# MirrorController.net
KiCad netlist of a schematic drawn in EAGLE
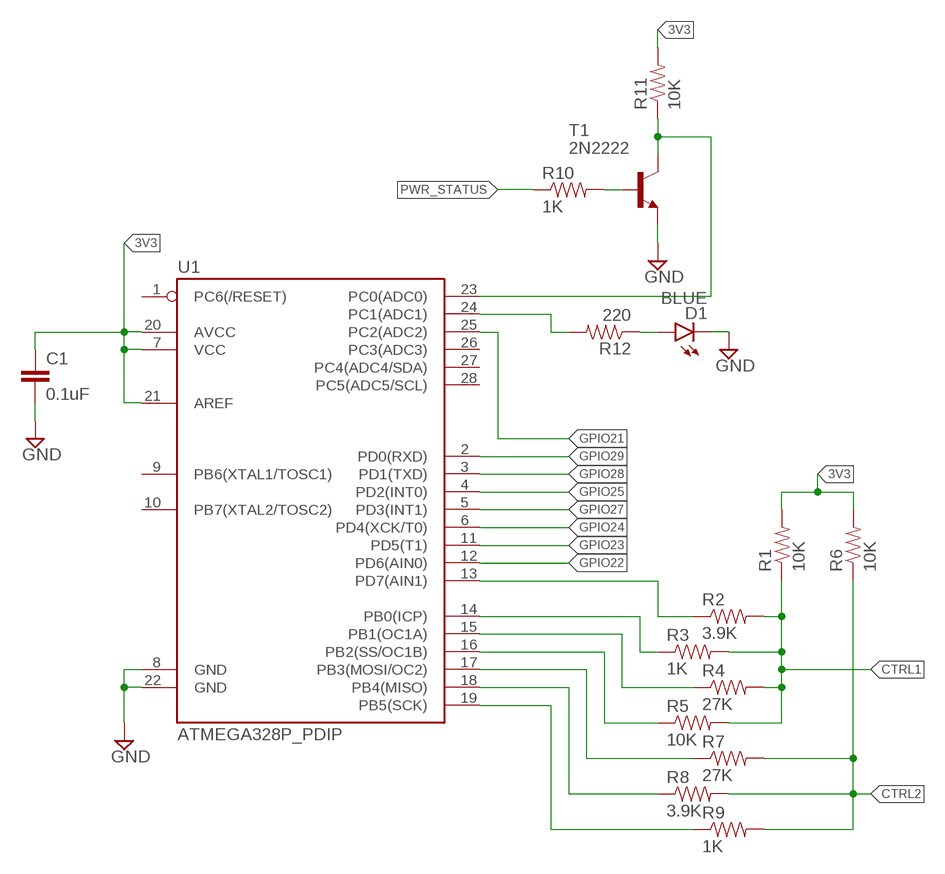
[diagram p0: schematic, sheet 1]

(export (version "E")
  (design (tool "Eeschema 10.0.6"))
  (components
    (comp (ref "C1")
      (value "0.1uF")
      (footprint "eagle-import:CAP-PTH-SMALL")
      (libsource (lib "eagle-import") (part "CAPPTH"))
    )
    (comp (ref "D1")
      (value "BLUE")
      (footprint "eagle-import:LED5MM")
      (libsource (lib "eagle-import") (part "LED5MM"))
    )
    (comp (ref "R1")
      (value "10K")
      (footprint "eagle-import:AXIAL-0.4")
      (libsource (lib "eagle-import") (part "RESISTORPTH-1/4W"))
    )
    (comp (ref "R2")
      (value "3.9K")
      (footprint "eagle-import:AXIAL-0.4")
      (libsource (lib "eagle-import") (part "RESISTORPTH-1/4W"))
    )
    (comp (ref "R3")
      (value "1K")
      (footprint "eagle-import:AXIAL-0.4")
      (libsource (lib "eagle-import") (part "RESISTORPTH-1/4W"))
    )
    (comp (ref "R4")
      (value "27K")
      (footprint "eagle-import:AXIAL-0.4")
      (libsource (lib "eagle-import") (part "RESISTORPTH-1/4W"))
    )
    (comp (ref "R5")
      (value "10K")
      (footprint "eagle-import:AXIAL-0.4")
      (libsource (lib "eagle-import") (part "RESISTORPTH-1/4W"))
    )
    (comp (ref "R6")
      (value "10K")
      (footprint "eagle-import:AXIAL-0.4")
      (libsource (lib "eagle-import") (part "RESISTORPTH-1/4W"))
    )
    (comp (ref "R7")
      (value "27K")
      (footprint "eagle-import:AXIAL-0.4")
      (libsource (lib "eagle-import") (part "RESISTORPTH-1/4W"))
    )
    (comp (ref "R8")
      (value "3.9K")
      (footprint "eagle-import:AXIAL-0.4")
      (libsource (lib "eagle-import") (part "RESISTORPTH-1/4W"))
    )
    (comp (ref "R9")
      (value "1K")
      (footprint "eagle-import:AXIAL-0.4")
      (libsource (lib "eagle-import") (part "RESISTORPTH-1/4W"))
    )
    (comp (ref "R10")
      (value "1K")
      (footprint "eagle-import:AXIAL-0.4")
      (libsource (lib "eagle-import") (part "RESISTORPTH-1/4W"))
    )
    (comp (ref "R11")
      (value "10K")
      (footprint "eagle-import:AXIAL-0.4")
      (libsource (lib "eagle-import") (part "RESISTORPTH-1/4W"))
    )
    (comp (ref "R12")
      (value "220")
      (footprint "eagle-import:AXIAL-0.4")
      (libsource (lib "eagle-import") (part "RESISTORPTH-1/4W"))
    )
    (comp (ref "T1")
      (value "2N2222")
      (footprint "eagle-import:TO92-EBC-OVAL")
      (libsource (lib "eagle-import") (part "2N2222"))
    )
    (comp (ref "U1")
      (value "ATMEGA328P_PDIP")
      (footprint "eagle-import:DIL28-3")
      (libsource (lib "eagle-import") (part "ATMEGA328P_PDIP"))
    )
  )
  (nets
    (net (code "1") (name "3V3") (class "Default")
      (node (ref "C1") (pin "1") (pinfunction "1_1") (pintype "passive"))
      (node (ref "R1") (pin "P$2") (pinfunction "2_P$2") (pintype "passive"))
      (node (ref "R11") (pin "P$2") (pinfunction "2_P$2") (pintype "passive"))
      (node (ref "R6") (pin "P$2") (pinfunction "2_P$2") (pintype "passive"))
      (node (ref "U1") (pin "20") (pinfunction "AVCC_20") (pintype "bidirectional"))
      (node (ref "U1") (pin "21") (pinfunction "AREF_21") (pintype "bidirectional"))
      (node (ref "U1") (pin "7") (pinfunction "VCC_7") (pintype "bidirectional"))
    )
    (net (code "2") (name "CTRL1") (class "Default")
      (node (ref "R1") (pin "P$1") (pinfunction "1_P$1") (pintype "passive"))
      (node (ref "R2") (pin "P$2") (pinfunction "2_P$2") (pintype "passive"))
      (node (ref "R3") (pin "P$2") (pinfunction "2_P$2") (pintype "passive"))
      (node (ref "R4") (pin "P$2") (pinfunction "2_P$2") (pintype "passive"))
      (node (ref "R5") (pin "P$2") (pinfunction "2_P$2") (pintype "passive"))
    )
    (net (code "3") (name "CTRL2") (class "Default")
      (node (ref "R6") (pin "P$1") (pinfunction "1_P$1") (pintype "passive"))
      (node (ref "R7") (pin "P$2") (pinfunction "2_P$2") (pintype "passive"))
      (node (ref "R8") (pin "P$2") (pinfunction "2_P$2") (pintype "passive"))
      (node (ref "R9") (pin "P$2") (pinfunction "2_P$2") (pintype "passive"))
    )
    (net (code "4") (name "GND") (class "Default")
      (node (ref "C1") (pin "2") (pinfunction "2_2") (pintype "passive"))
      (node (ref "D1") (pin "K") (pinfunction "C_K") (pintype "passive"))
      (node (ref "T1") (pin "E") (pinfunction "E_E") (pintype "passive"))
      (node (ref "U1") (pin "22") (pinfunction "GND_22") (pintype "bidirectional"))
      (node (ref "U1") (pin "8") (pinfunction "GND_8") (pintype "bidirectional"))
    )
    (net (code "5") (name "GPIO21") (class "Default")
      (node (ref "U1") (pin "25") (pinfunction "PC2(ADC2)_25") (pintype "bidirectional"))
    )
    (net (code "6") (name "GPIO22") (class "Default")
      (node (ref "U1") (pin "12") (pinfunction "PD6(AIN0)_12") (pintype "bidirectional"))
    )
    (net (code "7") (name "GPIO23") (class "Default")
      (node (ref "U1") (pin "11") (pinfunction "PD5(T1)_11") (pintype "bidirectional"))
    )
    (net (code "8") (name "GPIO24") (class "Default")
      (node (ref "U1") (pin "6") (pinfunction "PD4(XCK/T0)_6") (pintype "bidirectional"))
    )
    (net (code "9") (name "GPIO25") (class "Default")
      (node (ref "U1") (pin "4") (pinfunction "PD2(INT0)_4") (pintype "bidirectional"))
    )
    (net (code "10") (name "GPIO27") (class "Default")
      (node (ref "U1") (pin "5") (pinfunction "PD3(INT1)_5") (pintype "bidirectional"))
    )
    (net (code "11") (name "GPIO28") (class "Default")
      (node (ref "U1") (pin "3") (pinfunction "PD1(TXD)_3") (pintype "bidirectional"))
    )
    (net (code "12") (name "GPIO29") (class "Default")
      (node (ref "U1") (pin "2") (pinfunction "PD0(RXD)_2") (pintype "bidirectional"))
    )
    (net (code "13") (name "Net-(R2-1)") (class "Default")
      (node (ref "R2") (pin "P$1") (pinfunction "1_P$1") (pintype "passive"))
      (node (ref "U1") (pin "13") (pinfunction "PD7(AIN1)_13") (pintype "bidirectional"))
    )
    (net (code "14") (name "Net-(R3-1)") (class "Default")
      (node (ref "R3") (pin "P$1") (pinfunction "1_P$1") (pintype "passive"))
      (node (ref "U1") (pin "14") (pinfunction "PB0(ICP)_14") (pintype "bidirectional"))
    )
    (net (code "15") (name "Net-(R4-1)") (class "Default")
      (node (ref "R4") (pin "P$1") (pinfunction "1_P$1") (pintype "passive"))
      (node (ref "U1") (pin "15") (pinfunction "PB1(OC1A)_15") (pintype "bidirectional"))
    )
    (net (code "16") (name "Net-(R5-1)") (class "Default")
      (node (ref "R5") (pin "P$1") (pinfunction "1_P$1") (pintype "passive"))
      (node (ref "U1") (pin "16") (pinfunction "PB2(SS/OC1B)_16") (pintype "bidirectional"))
    )
    (net (code "17") (name "Net-(R7-1)") (class "Default")
      (node (ref "R7") (pin "P$1") (pinfunction "1_P$1") (pintype "passive"))
      (node (ref "U1") (pin "17") (pinfunction "PB3(MOSI/OC2)_17") (pintype "bidirectional"))
    )
    (net (code "18") (name "Net-(R8-1)") (class "Default")
      (node (ref "R8") (pin "P$1") (pinfunction "1_P$1") (pintype "passive"))
      (node (ref "U1") (pin "18") (pinfunction "PB4(MISO)_18") (pintype "bidirectional"))
    )
    (net (code "19") (name "Net-(R9-1)") (class "Default")
      (node (ref "R9") (pin "P$1") (pinfunction "1_P$1") (pintype "passive"))
      (node (ref "U1") (pin "19") (pinfunction "PB5(SCK)_19") (pintype "bidirectional"))
    )
    (net (code "20") (name "Net-(R10-2)") (class "Default")
      (node (ref "R10") (pin "P$2") (pinfunction "2_P$2") (pintype "passive"))
      (node (ref "T1") (pin "B") (pinfunction "B_B") (pintype "passive"))
    )
    (net (code "21") (name "Net-(R11-1)") (class "Default")
      (node (ref "R11") (pin "P$1") (pinfunction "1_P$1") (pintype "passive"))
      (node (ref "T1") (pin "C") (pinfunction "C_C") (pintype "passive"))
      (node (ref "U1") (pin "23") (pinfunction "PC0(ADC0)_23") (pintype "bidirectional"))
    )
    (net (code "22") (name "Net-(R12-1)") (class "Default")
      (node (ref "D1") (pin "A") (pinfunction "A_A") (pintype "passive"))
      (node (ref "R12") (pin "P$1") (pinfunction "1_P$1") (pintype "passive"))
    )
    (net (code "23") (name "Net-(R12-2)") (class "Default")
      (node (ref "R12") (pin "P$2") (pinfunction "2_P$2") (pintype "passive"))
      (node (ref "U1") (pin "24") (pinfunction "PC1(ADC1)_24") (pintype "bidirectional"))
    )
    (net (code "24") (name "PWR_STATUS") (class "Default")
      (node (ref "R10") (pin "P$1") (pinfunction "1_P$1") (pintype "passive"))
    )
    (net (code "25") (name "unconnected-(U1-PB6(XTAL1{slash}TOSC1)-Pad9)") (class "Default")
      (node (ref "U1") (pin "9") (pinfunction "PB6(XTAL1/TOSC1)_9") (pintype "bidirectional"))
    )
    (net (code "26") (name "unconnected-(U1-PB7(XTAL2{slash}TOSC2)-Pad10)") (class "Default")
      (node (ref "U1") (pin "10") (pinfunction "PB7(XTAL2/TOSC2)_10") (pintype "bidirectional"))
    )
    (net (code "27") (name "unconnected-(U1-PC3(ADC3)-Pad26)") (class "Default")
      (node (ref "U1") (pin "26") (pinfunction "PC3(ADC3)_26") (pintype "bidirectional"))
    )
    (net (code "28") (name "unconnected-(U1-PC4(ADC4{slash}SDA)-Pad27)") (class "Default")
      (node (ref "U1") (pin "27") (pinfunction "PC4(ADC4/SDA)_27") (pintype "bidirectional"))
    )
    (net (code "29") (name "unconnected-(U1-PC5(ADC5{slash}SCL)-Pad28)") (class "Default")
      (node (ref "U1") (pin "28") (pinfunction "PC5(ADC5/SCL)_28") (pintype "bidirectional"))
    )
    (net (code "30") (name "unconnected-(U1-PC6({slash}RESET)-Pad1)") (class "Default")
      (node (ref "U1") (pin "1") (pinfunction "PC6(/RESET)_1") (pintype "bidirectional"))
    )
  )
)
